# leds_and_button.net
KiCad netlist of a schematic drawn in EAGLE
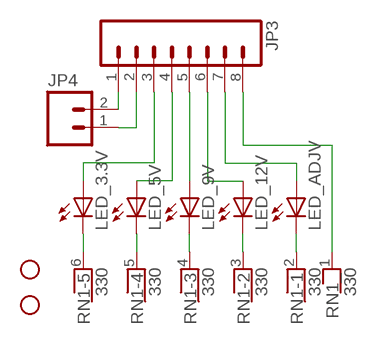
[diagram p0: schematic, sheet 1]

(export (version "E")
  (design (tool "Eeschema 10.0.6"))
  (components
    (comp (ref "JP1")
      (value "STAND-OFF")
      (footprint "eagle-import:STAND-OFF")
      (libsource (lib "eagle-import") (part "STAND-OFF"))
    )
    (comp (ref "JP2")
      (value "STAND-OFF")
      (footprint "eagle-import:STAND-OFF")
      (libsource (lib "eagle-import") (part "STAND-OFF"))
    )
    (comp (ref "JP3")
      (value "M081X08")
      (footprint "eagle-import:1X08")
      (libsource (lib "eagle-import") (part "M081X08"))
    )
    (comp (ref "JP4")
      (value "M02PTH")
      (footprint "eagle-import:1X02")
      (libsource (lib "eagle-import") (part "M02PTH"))
    )
    (comp (ref "LED_3.3V")
      (value "LED-3MM-NO_SILK")
      (footprint "eagle-import:LED3MM-NS")
      (libsource (lib "eagle-import") (part "LED-3MM-NO_SILK"))
    )
    (comp (ref "LED_5V")
      (value "LED-3MM-NO_SILK")
      (footprint "eagle-import:LED3MM-NS")
      (libsource (lib "eagle-import") (part "LED-3MM-NO_SILK"))
    )
    (comp (ref "LED_9V")
      (value "LED-3MM-NO_SILK")
      (footprint "eagle-import:LED3MM-NS")
      (libsource (lib "eagle-import") (part "LED-3MM-NO_SILK"))
    )
    (comp (ref "LED_12V")
      (value "LED-3MM-NO_SILK")
      (footprint "eagle-import:LED3MM-NS")
      (libsource (lib "eagle-import") (part "LED-3MM-NO_SILK"))
    )
    (comp (ref "LED_ADJV")
      (value "LED-3MM-NO_SILK")
      (footprint "eagle-import:LED3MM-NS")
      (libsource (lib "eagle-import") (part "LED-3MM-NO_SILK"))
    )
    (comp (ref "RN1")
      (value "330")
      (footprint "eagle-import:RN-6")
      (libsource (lib "eagle-import") (part "RNX5"))
    )
  )
  (nets
    (net (code "1") (name "Net-(JP3-Pad1)") (class "Default")
      (node (ref "JP3") (pin "1") (pinfunction "1_1") (pintype "passive"))
      (node (ref "JP4") (pin "2") (pinfunction "2_2") (pintype "passive"))
    )
    (net (code "2") (name "Net-(JP3-Pad2)") (class "Default")
      (node (ref "JP3") (pin "2") (pinfunction "2_2") (pintype "passive"))
      (node (ref "JP4") (pin "1") (pinfunction "1_1") (pintype "passive"))
    )
    (net (code "3") (name "Net-(JP3-Pad3)") (class "Default")
      (node (ref "JP3") (pin "3") (pinfunction "3_3") (pintype "passive"))
      (node (ref "LED_3.3V") (pin "A") (pinfunction "A_A") (pintype "passive"))
    )
    (net (code "4") (name "Net-(JP3-Pad4)") (class "Default")
      (node (ref "JP3") (pin "4") (pinfunction "4_4") (pintype "passive"))
      (node (ref "LED_5V") (pin "A") (pinfunction "A_A") (pintype "passive"))
    )
    (net (code "5") (name "Net-(JP3-Pad5)") (class "Default")
      (node (ref "JP3") (pin "5") (pinfunction "5_5") (pintype "passive"))
      (node (ref "LED_9V") (pin "A") (pinfunction "A_A") (pintype "passive"))
    )
    (net (code "6") (name "Net-(JP3-Pad6)") (class "Default")
      (node (ref "JP3") (pin "6") (pinfunction "6_6") (pintype "passive"))
      (node (ref "LED_12V") (pin "A") (pinfunction "A_A") (pintype "passive"))
    )
    (net (code "7") (name "Net-(JP3-Pad7)") (class "Default")
      (node (ref "JP3") (pin "7") (pinfunction "7_7") (pintype "passive"))
      (node (ref "LED_ADJV") (pin "A") (pinfunction "A_A") (pintype "passive"))
    )
    (net (code "8") (name "Net-(JP3-Pad8)") (class "Default")
      (node (ref "JP3") (pin "8") (pinfunction "8_8") (pintype "passive"))
      (node (ref "RN1") (pin "1") (pinfunction "1_1") (pintype "passive"))
    )
    (net (code "9") (name "Net-(LED_3.3V-C)") (class "Default")
      (node (ref "LED_3.3V") (pin "K") (pinfunction "C_K") (pintype "passive"))
      (node (ref "RN1") (pin "6") (pinfunction "1_6") (pintype "passive"))
    )
    (net (code "10") (name "Net-(LED_5V-C)") (class "Default")
      (node (ref "LED_5V") (pin "K") (pinfunction "C_K") (pintype "passive"))
      (node (ref "RN1") (pin "5") (pinfunction "1_5") (pintype "passive"))
    )
    (net (code "11") (name "Net-(LED_9V-C)") (class "Default")
      (node (ref "LED_9V") (pin "K") (pinfunction "C_K") (pintype "passive"))
      (node (ref "RN1") (pin "4") (pinfunction "1_4") (pintype "passive"))
    )
    (net (code "12") (name "Net-(LED_12V-C)") (class "Default")
      (node (ref "LED_12V") (pin "K") (pinfunction "C_K") (pintype "passive"))
      (node (ref "RN1") (pin "3") (pinfunction "1_3") (pintype "passive"))
    )
    (net (code "13") (name "Net-(LED_ADJV-C)") (class "Default")
      (node (ref "LED_ADJV") (pin "K") (pinfunction "C_K") (pintype "passive"))
      (node (ref "RN1") (pin "2") (pinfunction "1_2") (pintype "passive"))
    )
  )
)
